# 01_Microcontroller_Circuit.net
KiCad netlist of a schematic drawn in Altium Designer
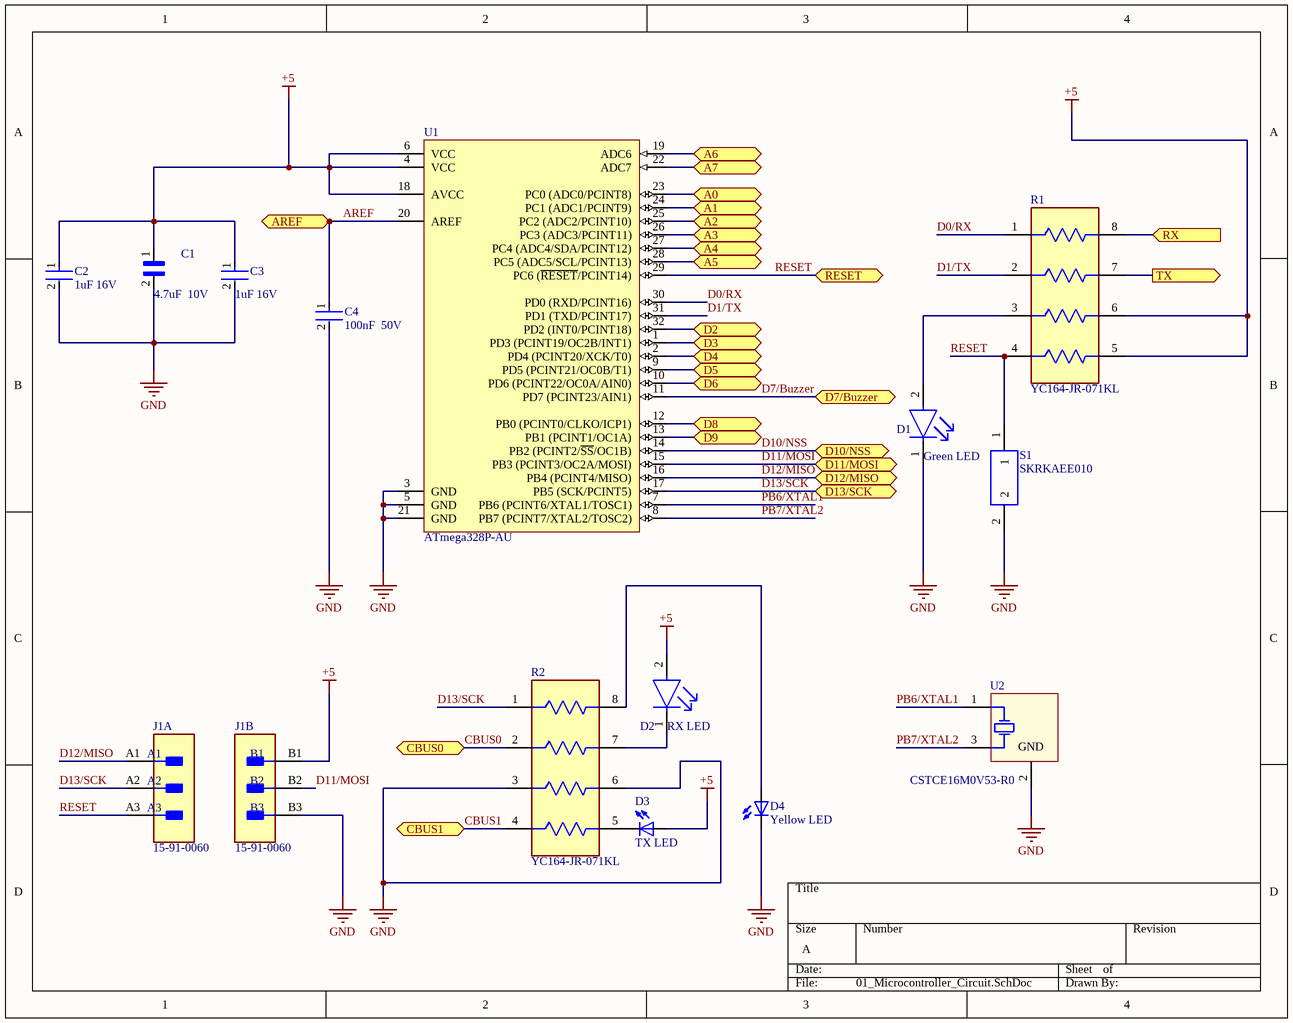
[diagram p0: 01_Microcontroller_Circuit.SchDoc]

(export (version "E")
  (design (tool "Eeschema 10.0.6"))
  (components
    (comp (ref "C1")
      (value "4.7uF  10V")
      (footprint "CAPC1608X90")
      (libsource (lib "CC0603ZRY5V5BB475") (part "CC0603ZRY5V5BB475"))
    )
    (comp (ref "C2")
      (value "1uF 16V")
      (footprint "FP-CL10B105KO8NNNC-MFG")
      (description "CAP CER 1UF 16V X7R 0603")
      (fields
        (field (name "OCTOPART") "https://octopart.com/cl10b105ko8nnnc-samsung-19018973")
        (field (name "MANUFACTURER") "Samsung Electro-Mechanics America, Inc")
      )
      (libsource (lib "Altium Content Vault") (part "b4654b650e69147ec39a6b967a45e02"))
    )
    (comp (ref "C3")
      (value "1uF 16V")
      (footprint "FP-CL10B105KO8NNNC-MFG")
      (description "CAP CER 1UF 16V X7R 0603")
      (fields
        (field (name "OCTOPART") "https://octopart.com/cl10b105ko8nnnc-samsung-19018973")
        (field (name "MANUFACTURER") "Samsung Electro-Mechanics America, Inc")
      )
      (libsource (lib "Altium Content Vault") (part "b4654b650e69147ec39a6b967a45e02"))
    )
    (comp (ref "C4")
      (value "100nF  50V")
      (footprint "FP-0805-L_2_01_0_2-W_1_25-IPC_C")
      (description "General Purpose Ceramic Capacitor, 0805, 100nF, 10%, X7R, 0.15, 50V")
      (fields (field (name "TOLERANCE") "10%") (field (name "VOLTAGE") "50V"))
      (libsource (lib "Altium Content Vault") (part "02cd4be3c70576c341d710602a673aa"))
    )
    (comp (ref "D1")
      (value "Green LED")
      (footprint "FP-LTST-C171KGKT-MFG")
      (description "LED GREEN CLEAR SMD")
      (libsource (lib "Altium Content Vault") (part "8706943c75ba83719d021d2fdc84c58"))
    )
    (comp (ref "D2")
      (value "RX LED")
      (footprint "FP-LTST-C171KGKT-MFG")
      (description "LED GREEN CLEAR SMD")
      (libsource (lib "Altium Content Vault") (part "8706943c75ba83719d021d2fdc84c58"))
    )
    (comp (ref "D3")
      (value "TX LED")
      (footprint "DIOC200X125X110")
      (description "Yellow 587nm LED Indication - Discrete 2V 0805 (2012 Metric)")
      (fields (field (name "MF") "Lite-On Inc.") (field (name "MP") "LTST-C171KSKT"))
      (libsource (lib "RFID") (part "LTST-C171KSKT"))
    )
    (comp (ref "D4")
      (value "Yellow LED")
      (footprint "DIOC200X125X110")
      (description "Yellow 587nm LED Indication - Discrete 2V 0805 (2012 Metric)")
      (fields (field (name "MF") "Lite-On Inc.") (field (name "MP") "LTST-C171KSKT"))
      (libsource (lib "RFID") (part "LTST-C171KSKT"))
    )
    (comp (ref "J1")
      (value "15-91-0060")
      (footprint "FP-15-91-0060-MFG")
      (description "CONN HEADER SMD 6POS 2.54MM")
      (libsource (lib "Altium Content Vault") (part "d67bc6b65130272fd4c4cbacc1ef78e"))
    )
    (comp (ref "R1")
      (value "YC164-JR-071KL")
      (footprint "FP-YC164-MFG")
      (description "RES ARRAY 4 RES 1K OHM 1206")
      (fields (field (name "TOLERANCE") "5%"))
      (libsource (lib "Altium Content Vault") (part "b65cf3291297dcf86d9c7c269206e6b"))
    )
    (comp (ref "R2")
      (value "YC164-JR-071KL")
      (footprint "FP-YC164-MFG")
      (description "RES ARRAY 4 RES 1K OHM 1206")
      (fields (field (name "TOLERANCE") "5%"))
      (libsource (lib "Altium Content Vault") (part "b65cf3291297dcf86d9c7c269206e6b"))
    )
    (comp (ref "S1")
      (value "SKRKAEE010")
      (footprint "SKRK")
      (description "Switch Tactile N.O. SPST Round Button Gull Wing 0.05A 12VDC 1.57N SMD T/R")
      (fields (field (name "MF") "ALPS"))
      (libsource (lib "SKRKAEE010") (part "SKRKAEE010"))
    )
    (comp (ref "U1")
      (value "ATmega328P-AU")
      (footprint "32A_M")
      (libsource (lib "Altium Content Vault") (part "MC-8B-ATM48-SQ32"))
    )
    (comp (ref "U2")
      (value "CSTCE16M0V53-R0")
      (footprint "MURA-CSTCE_V-3_V")
      (fields (field (name "MANUFACTURER") "Murata"))
      (libsource (lib "Altium Content Vault") (part "MURA-CSTCE_V-3"))
    )
  )
  (nets
    (net (code "1") (name "+5") (class "Default")
      (node (ref "C1") (pin "1") (pinfunction "1_1") (pintype "passive"))
      (node (ref "C2") (pin "1") (pinfunction "1_1") (pintype "passive"))
      (node (ref "C3") (pin "1") (pinfunction "1_1") (pintype "passive"))
      (node (ref "D2") (pin "2") (pinfunction "A_2") (pintype "passive"))
      (node (ref "D3") (pin "POS") (pinfunction "POS_POS") (pintype "passive"))
      (node (ref "J1") (pin "B1") (pinfunction "B1_B1") (pintype "passive"))
      (node (ref "R1") (pin "5") (pinfunction "5_5") (pintype "passive"))
      (node (ref "R1") (pin "6") (pinfunction "6_6") (pintype "passive"))
      (node (ref "U1") (pin "18") (pinfunction "AVCC_18") (pintype "power_in"))
      (node (ref "U1") (pin "4") (pinfunction "VCC_4") (pintype "power_in"))
      (node (ref "U1") (pin "6") (pinfunction "VCC_6") (pintype "power_in"))
    )
    (net (code "2") (name "/A0") (class "Default")
      (node (ref "U1") (pin "23") (pinfunction "PC0_(ADC0/PCINT8)_23") (pintype "bidirectional"))
    )
    (net (code "3") (name "/A1") (class "Default")
      (node (ref "U1") (pin "24") (pinfunction "PC1_(ADC1/PCINT9)_24") (pintype "bidirectional"))
    )
    (net (code "4") (name "/A2") (class "Default")
      (node (ref "U1") (pin "25") (pinfunction "PC2_(ADC2/PCINT10)_25") (pintype "bidirectional"))
    )
    (net (code "5") (name "/A3") (class "Default")
      (node (ref "U1") (pin "26") (pinfunction "PC3_(ADC3/PCINT11)_26") (pintype "bidirectional"))
    )
    (net (code "6") (name "/A4") (class "Default")
      (node (ref "U1") (pin "27") (pinfunction "PC4_(ADC4/SDA/PCINT12)_27") (pintype "bidirectional"))
    )
    (net (code "7") (name "/A5") (class "Default")
      (node (ref "U1") (pin "28") (pinfunction "PC5_(ADC5/SCL/PCINT13)_28") (pintype "bidirectional"))
    )
    (net (code "8") (name "/A6") (class "Default")
      (node (ref "U1") (pin "19") (pinfunction "ADC6_19") (pintype "input"))
    )
    (net (code "9") (name "/A7") (class "Default")
      (node (ref "U1") (pin "22") (pinfunction "ADC7_22") (pintype "input"))
    )
    (net (code "10") (name "/AREF") (class "Default")
      (node (ref "C4") (pin "1") (pinfunction "1_1") (pintype "passive"))
      (node (ref "U1") (pin "20") (pinfunction "AREF_20") (pintype "passive"))
    )
    (net (code "11") (name "/CBUS0") (class "Default")
      (node (ref "R2") (pin "2") (pinfunction "2_2") (pintype "passive"))
    )
    (net (code "12") (name "/CBUS1") (class "Default")
      (node (ref "R2") (pin "4") (pinfunction "4_4") (pintype "passive"))
    )
    (net (code "13") (name "/D0{slash}RX") (class "Default")
      (node (ref "R1") (pin "1") (pinfunction "1_1") (pintype "passive"))
      (node (ref "U1") (pin "30") (pinfunction "PD0_(RXD/PCINT16)_30") (pintype "bidirectional"))
    )
    (net (code "14") (name "/D1{slash}TX") (class "Default")
      (node (ref "R1") (pin "2") (pinfunction "2_2") (pintype "passive"))
      (node (ref "U1") (pin "31") (pinfunction "PD1_(TXD/PCINT17)_31") (pintype "bidirectional"))
    )
    (net (code "15") (name "/D2") (class "Default")
      (node (ref "U1") (pin "32") (pinfunction "PD2_(INT0/PCINT18)_32") (pintype "bidirectional"))
    )
    (net (code "16") (name "/D3") (class "Default")
      (node (ref "U1") (pin "1") (pinfunction "PD3_(PCINT19/OC2B/INT1)_1") (pintype "bidirectional"))
    )
    (net (code "17") (name "/D4") (class "Default")
      (node (ref "U1") (pin "2") (pinfunction "PD4_(PCINT20/XCK/T0)_2") (pintype "bidirectional"))
    )
    (net (code "18") (name "/D5") (class "Default")
      (node (ref "U1") (pin "9") (pinfunction "PD5_(PCINT21/OC0B/T1)_9") (pintype "bidirectional"))
    )
    (net (code "19") (name "/D6") (class "Default")
      (node (ref "U1") (pin "10") (pinfunction "PD6_(PCINT22/OC0A/AIN0)_10") (pintype "bidirectional"))
    )
    (net (code "20") (name "/D7{slash}Buzzer") (class "Default")
      (node (ref "U1") (pin "11") (pinfunction "PD7_(PCINT23/AIN1)_11") (pintype "bidirectional"))
    )
    (net (code "21") (name "/D8") (class "Default")
      (node (ref "U1") (pin "12") (pinfunction "PB0_(PCINT0/CLKO/ICP1)_12") (pintype "bidirectional"))
    )
    (net (code "22") (name "/D9") (class "Default")
      (node (ref "U1") (pin "13") (pinfunction "PB1_(PCINT1/OC1A)_13") (pintype "bidirectional"))
    )
    (net (code "23") (name "/D10{slash}NSS") (class "Default")
      (node (ref "U1") (pin "14") (pinfunction "PB2_(PCINT2/~{SS}/OC1B)_14") (pintype "bidirectional"))
    )
    (net (code "24") (name "/D11{slash}MOSI") (class "Default")
      (node (ref "J1") (pin "B2") (pinfunction "B2_B2") (pintype "passive"))
      (node (ref "U1") (pin "15") (pinfunction "PB3_(PCINT3/OC2A/MOSI)_15") (pintype "bidirectional"))
    )
    (net (code "25") (name "/D12{slash}MISO") (class "Default")
      (node (ref "J1") (pin "A1") (pinfunction "A1_A1") (pintype "passive"))
      (node (ref "U1") (pin "16") (pinfunction "PB4_(PCINT4/MISO)_16") (pintype "bidirectional"))
    )
    (net (code "26") (name "/D13{slash}SCK") (class "Default")
      (node (ref "J1") (pin "A2") (pinfunction "A2_A2") (pintype "passive"))
      (node (ref "R2") (pin "1") (pinfunction "1_1") (pintype "passive"))
      (node (ref "U1") (pin "17") (pinfunction "PB5_(SCK/PCINT5)_17") (pintype "bidirectional"))
    )
    (net (code "27") (name "/PB6{slash}XTAL1") (class "Default")
      (node (ref "U1") (pin "7") (pinfunction "PB6_(PCINT6/XTAL1/TOSC1)_7") (pintype "bidirectional"))
      (node (ref "U2") (pin "1") (pinfunction "C1_1") (pintype "passive"))
    )
    (net (code "28") (name "/PB7{slash}XTAL2") (class "Default")
      (node (ref "U1") (pin "8") (pinfunction "PB7_(PCINT7/XTAL2/TOSC2)_8") (pintype "bidirectional"))
      (node (ref "U2") (pin "3") (pinfunction "C2_3") (pintype "passive"))
    )
    (net (code "29") (name "/RESET") (class "Default")
      (node (ref "J1") (pin "A3") (pinfunction "A3_A3") (pintype "passive"))
      (node (ref "R1") (pin "4") (pinfunction "4_4") (pintype "passive"))
      (node (ref "S1") (pin "1") (pinfunction "1_1") (pintype "passive"))
      (node (ref "U1") (pin "29") (pinfunction "PC6_(~{RESET}/PCINT14)_29") (pintype "bidirectional"))
    )
    (net (code "30") (name "/RX") (class "Default")
      (node (ref "R1") (pin "8") (pinfunction "8_8") (pintype "passive"))
    )
    (net (code "31") (name "/TX") (class "Default")
      (node (ref "R1") (pin "7") (pinfunction "7_7") (pintype "passive"))
    )
    (net (code "32") (name "GND") (class "Default")
      (node (ref "C1") (pin "2") (pinfunction "2_2") (pintype "passive"))
      (node (ref "C2") (pin "2") (pinfunction "2_2") (pintype "passive"))
      (node (ref "C3") (pin "2") (pinfunction "2_2") (pintype "passive"))
      (node (ref "C4") (pin "2") (pinfunction "2_2") (pintype "passive"))
      (node (ref "D1") (pin "1") (pinfunction "C_1") (pintype "passive"))
      (node (ref "D4") (pin "NEG") (pinfunction "NEG_NEG") (pintype "passive"))
      (node (ref "J1") (pin "B3") (pinfunction "B3_B3") (pintype "passive"))
      (node (ref "R2") (pin "3") (pinfunction "3_3") (pintype "passive"))
      (node (ref "R2") (pin "6") (pinfunction "6_6") (pintype "passive"))
      (node (ref "S1") (pin "2") (pinfunction "2_2") (pintype "passive"))
      (node (ref "U1") (pin "21") (pinfunction "GND_21") (pintype "power_in"))
      (node (ref "U1") (pin "3") (pinfunction "GND_3") (pintype "power_in"))
      (node (ref "U1") (pin "5") (pinfunction "GND_5") (pintype "power_in"))
      (node (ref "U2") (pin "2") (pinfunction "GND_2") (pintype "power_in"))
    )
    (net (code "33") (name "Net-(D1-A)") (class "Default")
      (node (ref "D1") (pin "2") (pinfunction "A_2") (pintype "passive"))
      (node (ref "R1") (pin "3") (pinfunction "3_3") (pintype "passive"))
    )
    (net (code "34") (name "Net-(D2-C)") (class "Default")
      (node (ref "D2") (pin "1") (pinfunction "C_1") (pintype "passive"))
      (node (ref "R2") (pin "7") (pinfunction "7_7") (pintype "passive"))
    )
    (net (code "35") (name "Net-(D3-PadNEG)") (class "Default")
      (node (ref "D3") (pin "NEG") (pinfunction "NEG_NEG") (pintype "passive"))
      (node (ref "R2") (pin "5") (pinfunction "5_5") (pintype "passive"))
    )
    (net (code "36") (name "Net-(D4-PadPOS)") (class "Default")
      (node (ref "D4") (pin "POS") (pinfunction "POS_POS") (pintype "passive"))
      (node (ref "R2") (pin "8") (pinfunction "8_8") (pintype "passive"))
    )
  )
)
